# Esquematico.net
KiCad netlist of a schematic drawn in Altium Designer
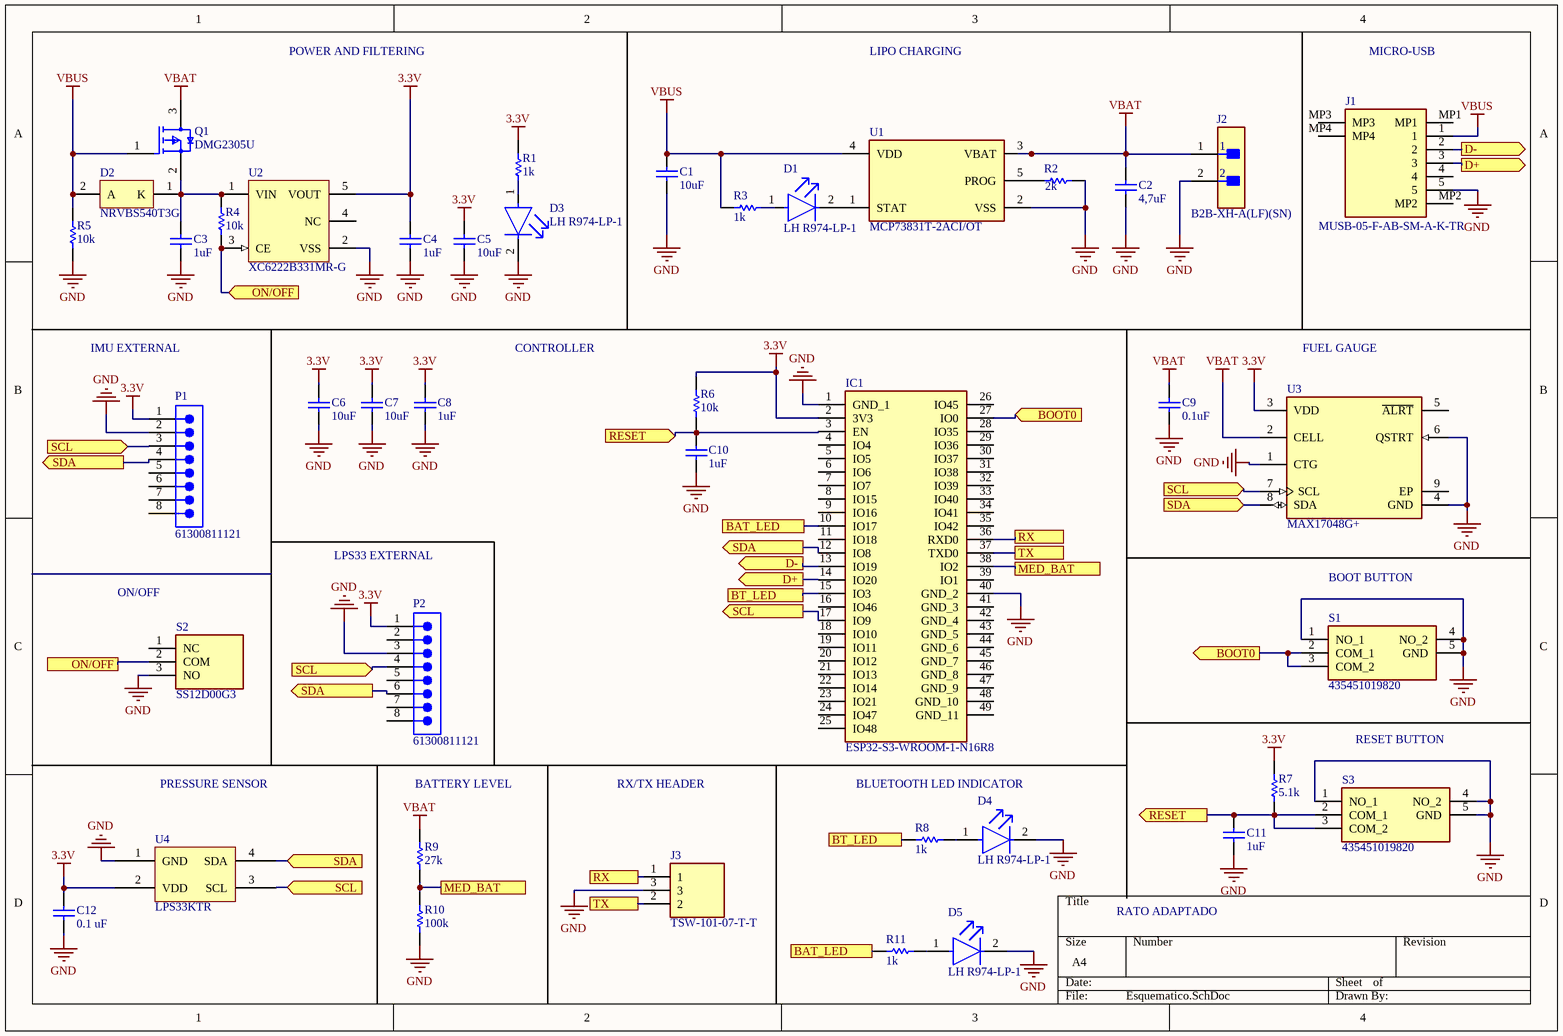
[diagram p0: Esquematico.SchDoc]

(export (version "E")
  (design (tool "Eeschema 10.0.6"))
  (components
    (comp (ref "C1")
      (value "10uF")
      (footprint "CAPC2013X88X50LL20T25")
      (fields (field (name "MANUFACTURER") "Kemet") (field (name "PART NUMBER") "C0805C103K5RACTU"))
      (libsource (lib "Altium Content Vault") (part "CAP"))
    )
    (comp (ref "C2")
      (value "4,7uF")
      (footprint "CAPC2013X88X50LL20T25")
      (fields (field (name "MANUFACTURER") "Kemet") (field (name "PART NUMBER") "C0805C103K5RACTU"))
      (libsource (lib "Altium Content Vault") (part "CAP"))
    )
    (comp (ref "C3")
      (value "1uF")
      (footprint "CAPC2013X88X50LL20T25")
      (fields (field (name "MANUFACTURER") "Kemet") (field (name "PART NUMBER") "C0805C103K5RACTU"))
      (libsource (lib "Altium Content Vault") (part "CAP"))
    )
    (comp (ref "C4")
      (value "1uF")
      (footprint "CAPC2013X88X50LL20T25")
      (fields (field (name "MANUFACTURER") "Kemet") (field (name "PART NUMBER") "C0805C103K5RACTU"))
      (libsource (lib "Altium Content Vault") (part "CAP"))
    )
    (comp (ref "C5")
      (value "10uF")
      (footprint "CAPC2013X88X50LL20T25")
      (fields (field (name "MANUFACTURER") "Kemet") (field (name "PART NUMBER") "C0805C103K5RACTU"))
      (libsource (lib "Altium Content Vault") (part "CAP"))
    )
    (comp (ref "C6")
      (value "10uF")
      (footprint "CAPC2013X88X50LL20T25")
      (fields (field (name "MANUFACTURER") "Kemet") (field (name "PART NUMBER") "C0805C103K5RACTU"))
      (libsource (lib "Altium Content Vault") (part "CAP"))
    )
    (comp (ref "C7")
      (value "10uF")
      (footprint "CAPC2013X88X50LL20T25")
      (fields (field (name "MANUFACTURER") "Kemet") (field (name "PART NUMBER") "C0805C103K5RACTU"))
      (libsource (lib "Altium Content Vault") (part "CAP"))
    )
    (comp (ref "C8")
      (value "1uF")
      (footprint "CAPC2013X88X50LL20T25")
      (fields (field (name "MANUFACTURER") "Kemet") (field (name "PART NUMBER") "C0805C103K5RACTU"))
      (libsource (lib "Altium Content Vault") (part "CAP"))
    )
    (comp (ref "C9")
      (value "0.1uF")
      (footprint "CAPC2013X88X50LL20T25")
      (fields (field (name "MANUFACTURER") "Kemet") (field (name "PART NUMBER") "C0805C103K5RACTU"))
      (libsource (lib "Altium Content Vault") (part "CAP"))
    )
    (comp (ref "C10")
      (value "1uF")
      (footprint "CAPC2013X88X50LL20T25")
      (fields (field (name "MANUFACTURER") "Kemet") (field (name "PART NUMBER") "C0805C103K5RACTU"))
      (libsource (lib "Altium Content Vault") (part "CAP"))
    )
    (comp (ref "C11")
      (value "1uF")
      (footprint "CAPC2013X88X50LL20T25")
      (fields (field (name "MANUFACTURER") "Kemet") (field (name "PART NUMBER") "C0805C103K5RACTU"))
      (libsource (lib "Altium Content Vault") (part "CAP"))
    )
    (comp (ref "C12")
      (value "0.1 uF")
      (footprint "CAPC2013X88X50LL20T25")
      (fields (field (name "MANUFACTURER") "Kemet") (field (name "PART NUMBER") "C0805C103K5RACTU"))
      (libsource (lib "Altium Content Vault") (part "CAP"))
    )
    (comp (ref "D1")
      (value "LH R974-LP-1")
      (footprint "FP-LH_R974-MFG")
      (description "LED RED DIFFUSED 0805 SMD")
      (libsource (lib "Altium Content Vault") (part "ab1c01a81903e929fc6c44469aada92"))
    )
    (comp (ref "D2")
      (value "NRVBS540T3G")
      (footprint "ONSC-SMC-2-403-03_V")
      (description "Schottky Power Rectifier, 2-Pin SMC, Pb-Free, Tape and Reel")
      (fields (field (name "MANUFACTURER") "On Semiconductor"))
      (libsource (lib "Altium Content Vault") (part "ONSC-D-K1A2-2_A"))
    )
    (comp (ref "D3")
      (value "LH R974-LP-1")
      (footprint "FP-LH_R974-MFG")
      (description "LED RED DIFFUSED 0805 SMD")
      (libsource (lib "Altium Content Vault") (part "ab1c01a81903e929fc6c44469aada92"))
    )
    (comp (ref "D4")
      (value "LH R974-LP-1")
      (footprint "FP-LH_R974-MFG")
      (description "LED RED DIFFUSED 0805 SMD")
      (libsource (lib "Altium Content Vault") (part "ab1c01a81903e929fc6c44469aada92"))
    )
    (comp (ref "D5")
      (value "LH R974-LP-1")
      (footprint "FP-LH_R974-MFG")
      (description "LED RED DIFFUSED 0805 SMD")
      (libsource (lib "Altium Content Vault") (part "ab1c01a81903e929fc6c44469aada92"))
    )
    (comp (ref "IC1")
      (value "ESP32-S3-WROOM-1-N16R8")
      (footprint "SamacSys:ESP32S3WROOM1N16R8")
      (description "Integrated Circuit")
      (fields (field (name "MOUSER PART NUMBER") "356-ESP32S3WRM1N16R8"))
      (libsource (lib "*") (part "ESP32-S3-WROOM-1-N16R8"))
    )
    (comp (ref "J1")
      (value "MUSB-05-F-AB-SM-A-K-TR")
      (footprint "SamacSys:MUSB05FABSMAKTR")
      (description "Connector")
      (fields (field (name "MOUSER PART NUMBER") "200-MUSB05FABSMAKTR"))
      (libsource (lib "*") (part "MUSB-05-F-AB-SM-A-K-TR"))
    )
    (comp (ref "J2")
      (value "B2B-XH-A(LF)(SN)")
      (footprint "FP-B2B-XH-A_LF_SN-MFG")
      (description "CONN HEADER VERT 2POS 2.5MM")
      (libsource (lib "Altium Content Vault") (part "3bc925449376181038e59eaffc5286c"))
    )
    (comp (ref "J3")
      (value "TSW-101-07-T-T")
      (footprint "SamacSys:HDRV3W64P254_3X1_254X762X838P")
      (description "Connector")
      (libsource (lib "*") (part "TSW-101-07-T-T"))
    )
    (comp (ref "P1")
      (value "61300811121")
      (footprint "61300811121")
      (libsource (lib "Altium Content Vault") (part "Header_Male_1R_08P"))
    )
    (comp (ref "P2")
      (value "61300811121")
      (footprint "61300811121")
      (libsource (lib "Altium Content Vault") (part "Header_Male_1R_08P"))
    )
    (comp (ref "Q1")
      (value "DMG2305U")
      (footprint "FP-SOT23-MFG")
      (description "MOSFET P-CH 20V 4.2A SOT23")
      (fields
        (field (name "MANUFACTURER") "Diodes Inc.")
        (field (name "MANUFACTURER PART NUMBER") "DMG2305UX-13")
      )
      (libsource (lib "Altium Content Vault") (part "b298ed0aef6ca29edb293456b19cad3"))
    )
    (comp (ref "R1")
      (value "1k")
      (footprint "RESC2013X50X30LL20T20")
      (fields (field (name "MANUFACTURER") "Vishay Dale") (field (name "PART NUMBER") "CRCW08050000Z0EA"))
      (libsource (lib "Altium Content Vault") (part "RES"))
    )
    (comp (ref "R2")
      (value "2k")
      (footprint "RESC2013X50X30LL20T20")
      (fields (field (name "MANUFACTURER") "Vishay Dale") (field (name "PART NUMBER") "CRCW08050000Z0EA"))
      (libsource (lib "Altium Content Vault") (part "RES"))
    )
    (comp (ref "R3")
      (value "1k")
      (footprint "RESC2013X50X30LL20T20")
      (fields (field (name "MANUFACTURER") "Vishay Dale") (field (name "PART NUMBER") "CRCW08050000Z0EA"))
      (libsource (lib "Altium Content Vault") (part "RES"))
    )
    (comp (ref "R4")
      (value "10k")
      (footprint "RESC2013X50X30LL20T20")
      (fields (field (name "MANUFACTURER") "Vishay Dale") (field (name "PART NUMBER") "CRCW08050000Z0EA"))
      (libsource (lib "Altium Content Vault") (part "RES"))
    )
    (comp (ref "R5")
      (value "10k")
      (footprint "RESC2013X50X30LL20T20")
      (fields (field (name "MANUFACTURER") "Vishay Dale") (field (name "PART NUMBER") "CRCW08050000Z0EA"))
      (libsource (lib "Altium Content Vault") (part "RES"))
    )
    (comp (ref "R6")
      (value "10k")
      (footprint "RESC2013X50X30LL20T20")
      (fields (field (name "MANUFACTURER") "Vishay Dale") (field (name "PART NUMBER") "CRCW08050000Z0EA"))
      (libsource (lib "Altium Content Vault") (part "RES"))
    )
    (comp (ref "R7")
      (value "5.1k")
      (footprint "RESC2013X50X30LL20T20")
      (fields (field (name "MANUFACTURER") "Vishay Dale") (field (name "PART NUMBER") "CRCW08050000Z0EA"))
      (libsource (lib "Altium Content Vault") (part "RES"))
    )
    (comp (ref "R8")
      (value "1k")
      (footprint "RESC2013X50X30LL20T20")
      (fields (field (name "MANUFACTURER") "Vishay Dale") (field (name "PART NUMBER") "CRCW08050000Z0EA"))
      (libsource (lib "Altium Content Vault") (part "RES"))
    )
    (comp (ref "R9")
      (value "27k")
      (footprint "RESC2013X50X30LL20T20")
      (fields (field (name "MANUFACTURER") "Vishay Dale") (field (name "PART NUMBER") "CRCW08050000Z0EA"))
      (libsource (lib "Altium Content Vault") (part "RES"))
    )
    (comp (ref "R10")
      (value "100k")
      (footprint "RESC2013X50X30LL20T20")
      (fields (field (name "MANUFACTURER") "Vishay Dale") (field (name "PART NUMBER") "CRCW08050000Z0EA"))
      (libsource (lib "Altium Content Vault") (part "RES"))
    )
    (comp (ref "R11")
      (value "1k")
      (footprint "RESC2013X50X30LL20T20")
      (fields (field (name "MANUFACTURER") "Vishay Dale") (field (name "PART NUMBER") "CRCW08050000Z0EA"))
      (libsource (lib "Altium Content Vault") (part "RES"))
    )
    (comp (ref "S1")
      (value "435451019820")
      (footprint "SamacSys:435451019820")
      (description "Switch")
      (fields (field (name "MOUSER PART NUMBER") "710-435451019820"))
      (libsource (lib "*") (part "435451019820"))
    )
    (comp (ref "S2")
      (value "SS12D00G3")
      (footprint "SamacSys:SS12D00G3")
      (description "Switch")
      (libsource (lib "*") (part "SS12D00G3"))
    )
    (comp (ref "S3")
      (value "435451019820")
      (footprint "SamacSys:435451019820")
      (description "Switch")
      (fields (field (name "MOUSER PART NUMBER") "710-435451019820"))
      (libsource (lib "*") (part "435451019820"))
    )
    (comp (ref "U1")
      (value "MCP73831T-2ACI/OT")
      (footprint "FP-C04-091-OT-IPC_B")
      (description "IC CONTROLLR LI-ION 4.2V SOT23-5")
      (libsource (lib "Altium Content Vault") (part "61f5a3bb3429d9e0caadea342aa3b19"))
    )
    (comp (ref "U2")
      (value "XC6222B331MR-G")
      (footprint "TORX-SOT-25-5_L")
      (description "High Speed LDO Regulator, 700 mA, 1.7 to 6.0 V, -40 to 85 degC, SOT-25 (MR-G), RoHS, Tape and Reel")
      (fields (field (name "MANUFACTURER") "Torex"))
      (libsource (lib "Altium Content Vault") (part "TORX-XC6222-SOT-25-5"))
    )
    (comp (ref "U3")
      (value "MAX17048G+")
      (footprint "FP-T822-3-MFG")
      (description "IC BATT MON LI-ION 1CELL 8TDFN")
      (libsource (lib "Altium Content Vault") (part "2e5dfe4d6b6c3eae1d63c902a28205a"))
    )
    (comp (ref "U4") (value "LPS33KTR") (footprint "LPS33KTR") (libsource (lib "LPS33KTR") (part "LPS33KTR")))
  )
  (nets
    (net (code "1") (name "/BAT_LED") (class "Default")
      (node (ref "IC1") (pin "10") (pinfunction "IO17_10") (pintype "passive"))
      (node (ref "R11") (pin "2") (pinfunction "2_2") (pintype "passive"))
    )
    (net (code "2") (name "/BOOT0") (class "Default")
      (node (ref "IC1") (pin "27") (pinfunction "IO0_27") (pintype "passive"))
      (node (ref "S1") (pin "2") (pinfunction "COM_1_2") (pintype "passive"))
      (node (ref "S1") (pin "3") (pinfunction "COM_2_3") (pintype "passive"))
    )
    (net (code "3") (name "/BT_LED") (class "Default")
      (node (ref "IC1") (pin "15") (pinfunction "IO3_15") (pintype "passive"))
      (node (ref "R8") (pin "2") (pinfunction "2_2") (pintype "passive"))
    )
    (net (code "4") (name "/D+") (class "Default")
      (node (ref "IC1") (pin "14") (pinfunction "IO20_14") (pintype "passive"))
      (node (ref "J1") (pin "3") (pinfunction "3_3") (pintype "passive"))
    )
    (net (code "5") (name "/D-") (class "Default")
      (node (ref "IC1") (pin "13") (pinfunction "IO19_13") (pintype "passive"))
      (node (ref "J1") (pin "2") (pinfunction "2_2") (pintype "passive"))
    )
    (net (code "6") (name "/MED_BAT") (class "Default")
      (node (ref "IC1") (pin "38") (pinfunction "IO2_38") (pintype "passive"))
      (node (ref "R10") (pin "2") (pinfunction "2_2") (pintype "passive"))
      (node (ref "R9") (pin "1") (pinfunction "1_1") (pintype "passive"))
    )
    (net (code "7") (name "/ON{slash}OFF") (class "Default")
      (node (ref "R4") (pin "1") (pinfunction "1_1") (pintype "passive"))
      (node (ref "S2") (pin "2") (pinfunction "COM_2") (pintype "passive"))
      (node (ref "U2") (pin "3") (pinfunction "CE_3") (pintype "input"))
    )
    (net (code "8") (name "/RESET") (class "Default")
      (node (ref "C10") (pin "2") (pinfunction "2_2") (pintype "passive"))
      (node (ref "C11") (pin "2") (pinfunction "2_2") (pintype "passive"))
      (node (ref "IC1") (pin "3") (pinfunction "EN_3") (pintype "passive"))
      (node (ref "R6") (pin "1") (pinfunction "1_1") (pintype "passive"))
      (node (ref "R7") (pin "2") (pinfunction "2_2") (pintype "passive"))
      (node (ref "S3") (pin "2") (pinfunction "COM_1_2") (pintype "passive"))
      (node (ref "S3") (pin "3") (pinfunction "COM_2_3") (pintype "passive"))
    )
    (net (code "9") (name "/RX") (class "Default")
      (node (ref "IC1") (pin "36") (pinfunction "RXD0_36") (pintype "passive"))
      (node (ref "J3") (pin "1") (pinfunction "1_1") (pintype "passive"))
    )
    (net (code "10") (name "/SCL") (class "Default")
      (node (ref "IC1") (pin "17") (pinfunction "IO9_17") (pintype "passive"))
      (node (ref "P1") (pin "3") (pinfunction "3_3") (pintype "passive"))
      (node (ref "P2") (pin "4") (pinfunction "4_4") (pintype "passive"))
      (node (ref "U3") (pin "7") (pinfunction "SCL_7") (pintype "input"))
      (node (ref "U4") (pin "3") (pinfunction "SCL_3") (pintype "passive"))
    )
    (net (code "11") (name "/SDA") (class "Default")
      (node (ref "IC1") (pin "12") (pinfunction "IO8_12") (pintype "passive"))
      (node (ref "P1") (pin "4") (pinfunction "4_4") (pintype "passive"))
      (node (ref "P2") (pin "6") (pinfunction "6_6") (pintype "passive"))
      (node (ref "U3") (pin "8") (pinfunction "SDA_8") (pintype "bidirectional"))
      (node (ref "U4") (pin "4") (pinfunction "SDA_4") (pintype "passive"))
    )
    (net (code "12") (name "/TX") (class "Default")
      (node (ref "IC1") (pin "37") (pinfunction "TXD0_37") (pintype "passive"))
      (node (ref "J3") (pin "2") (pinfunction "2_2") (pintype "passive"))
    )
    (net (code "13") (name "3.3V") (class "Default")
      (node (ref "C12") (pin "1") (pinfunction "1_1") (pintype "passive"))
      (node (ref "C4") (pin "2") (pinfunction "2_2") (pintype "passive"))
      (node (ref "C5") (pin "2") (pinfunction "2_2") (pintype "passive"))
      (node (ref "C6") (pin "2") (pinfunction "2_2") (pintype "passive"))
      (node (ref "C7") (pin "2") (pinfunction "2_2") (pintype "passive"))
      (node (ref "C8") (pin "2") (pinfunction "2_2") (pintype "passive"))
      (node (ref "IC1") (pin "2") (pinfunction "3V3_2") (pintype "passive"))
      (node (ref "P1") (pin "1") (pinfunction "1_1") (pintype "passive"))
      (node (ref "P2") (pin "1") (pinfunction "1_1") (pintype "passive"))
      (node (ref "R1") (pin "2") (pinfunction "2_2") (pintype "passive"))
      (node (ref "R6") (pin "2") (pinfunction "2_2") (pintype "passive"))
      (node (ref "R7") (pin "1") (pinfunction "1_1") (pintype "passive"))
      (node (ref "U2") (pin "5") (pinfunction "VOUT_5") (pintype "power_in"))
      (node (ref "U3") (pin "3") (pinfunction "VDD_3") (pintype "power_in"))
      (node (ref "U4") (pin "2") (pinfunction "VDD_2") (pintype "passive"))
    )
    (net (code "14") (name "GND") (class "Default")
      (node (ref "C1") (pin "1") (pinfunction "1_1") (pintype "passive"))
      (node (ref "C10") (pin "1") (pinfunction "1_1") (pintype "passive"))
      (node (ref "C11") (pin "1") (pinfunction "1_1") (pintype "passive"))
      (node (ref "C12") (pin "2") (pinfunction "2_2") (pintype "passive"))
      (node (ref "C2") (pin "1") (pinfunction "1_1") (pintype "passive"))
      (node (ref "C3") (pin "1") (pinfunction "1_1") (pintype "passive"))
      (node (ref "C4") (pin "1") (pinfunction "1_1") (pintype "passive"))
      (node (ref "C5") (pin "1") (pinfunction "1_1") (pintype "passive"))
      (node (ref "C6") (pin "1") (pinfunction "1_1") (pintype "passive"))
      (node (ref "C7") (pin "1") (pinfunction "1_1") (pintype "passive"))
      (node (ref "C8") (pin "1") (pinfunction "1_1") (pintype "passive"))
      (node (ref "C9") (pin "1") (pinfunction "1_1") (pintype "passive"))
      (node (ref "D3") (pin "2") (pinfunction "C_2") (pintype "passive"))
      (node (ref "D4") (pin "2") (pinfunction "C_2") (pintype "passive"))
      (node (ref "D5") (pin "2") (pinfunction "C_2") (pintype "passive"))
      (node (ref "IC1") (pin "1") (pinfunction "GND_1_1") (pintype "passive"))
      (node (ref "IC1") (pin "40") (pinfunction "GND_2_40") (pintype "passive"))
      (node (ref "J1") (pin "5") (pinfunction "5_5") (pintype "passive"))
      (node (ref "J2") (pin "2") (pinfunction "2_2") (pintype "passive"))
      (node (ref "J3") (pin "3") (pinfunction "3_3") (pintype "passive"))
      (node (ref "P1") (pin "2") (pinfunction "2_2") (pintype "passive"))
      (node (ref "P2") (pin "3") (pinfunction "3_3") (pintype "passive"))
      (node (ref "R10") (pin "1") (pinfunction "1_1") (pintype "passive"))
      (node (ref "R2") (pin "1") (pinfunction "1_1") (pintype "passive"))
      (node (ref "R5") (pin "1") (pinfunction "1_1") (pintype "passive"))
      (node (ref "S1") (pin "1") (pinfunction "NO_1_1") (pintype "passive"))
      (node (ref "S1") (pin "4") (pinfunction "NO_2_4") (pintype "passive"))
      (node (ref "S1") (pin "5") (pinfunction "GND_5") (pintype "passive"))
      (node (ref "S2") (pin "3") (pinfunction "NO_3") (pintype "passive"))
      (node (ref "S3") (pin "1") (pinfunction "NO_1_1") (pintype "passive"))
      (node (ref "S3") (pin "4") (pinfunction "NO_2_4") (pintype "passive"))
      (node (ref "S3") (pin "5") (pinfunction "GND_5") (pintype "passive"))
      (node (ref "U1") (pin "2") (pinfunction "VSS_2") (pintype "power_in"))
      (node (ref "U2") (pin "2") (pinfunction "VSS_2") (pintype "power_in"))
      (node (ref "U3") (pin "1") (pinfunction "CTG_1") (pintype "power_in"))
      (node (ref "U3") (pin "4") (pinfunction "GND_4") (pintype "power_in"))
      (node (ref "U3") (pin "6") (pinfunction "QSTRT_6") (pintype "input"))
      (node (ref "U4") (pin "1") (pinfunction "GND_1") (pintype "passive"))
    )
    (net (code "15") (name "Net-(D1-A)") (class "Default")
      (node (ref "D1") (pin "1") (pinfunction "A_1") (pintype "passive"))
      (node (ref "R3") (pin "1") (pinfunction "1_1") (pintype "passive"))
    )
    (net (code "16") (name "Net-(D1-C)") (class "Default")
      (node (ref "D1") (pin "2") (pinfunction "C_2") (pintype "passive"))
      (node (ref "U1") (pin "1") (pinfunction "STAT_1") (pintype "passive"))
    )
    (net (code "17") (name "Net-(D2-K)") (class "Default")
      (node (ref "C3") (pin "2") (pinfunction "2_2") (pintype "passive"))
      (node (ref "D2") (pin "1") (pinfunction "K_1") (pintype "passive"))
      (node (ref "Q1") (pin "2") (pinfunction "S_2") (pintype "passive"))
      (node (ref "R4") (pin "2") (pinfunction "2_2") (pintype "passive"))
      (node (ref "U2") (pin "1") (pinfunction "VIN_1") (pintype "power_in"))
    )
    (net (code "18") (name "Net-(D3-A)") (class "Default")
      (node (ref "D3") (pin "1") (pinfunction "A_1") (pintype "passive"))
      (node (ref "R1") (pin "1") (pinfunction "1_1") (pintype "passive"))
    )
    (net (code "19") (name "Net-(D4-A)") (class "Default")
      (node (ref "D4") (pin "1") (pinfunction "A_1") (pintype "passive"))
      (node (ref "R8") (pin "1") (pinfunction "1_1") (pintype "passive"))
    )
    (net (code "20") (name "Net-(D5-A)") (class "Default")
      (node (ref "D5") (pin "1") (pinfunction "A_1") (pintype "passive"))
      (node (ref "R11") (pin "1") (pinfunction "1_1") (pintype "passive"))
    )
    (net (code "21") (name "Net-(U1-PROG)") (class "Default")
      (node (ref "R2") (pin "2") (pinfunction "2_2") (pintype "passive"))
      (node (ref "U1") (pin "5") (pinfunction "PROG_5") (pintype "passive"))
    )
    (net (code "22") (name "VBAT") (class "Default")
      (node (ref "C2") (pin "2") (pinfunction "2_2") (pintype "passive"))
      (node (ref "C9") (pin "2") (pinfunction "2_2") (pintype "passive"))
      (node (ref "J2") (pin "1") (pinfunction "1_1") (pintype "passive"))
      (node (ref "Q1") (pin "3") (pinfunction "D_3") (pintype "passive"))
      (node (ref "R9") (pin "2") (pinfunction "2_2") (pintype "passive"))
      (node (ref "U1") (pin "3") (pinfunction "VBAT_3") (pintype "power_in"))
      (node (ref "U3") (pin "2") (pinfunction "CELL_2") (pintype "power_in"))
    )
    (net (code "23") (name "VBUS") (class "Default")
      (node (ref "C1") (pin "2") (pinfunction "2_2") (pintype "passive"))
      (node (ref "D2") (pin "2") (pinfunction "A_2") (pintype "passive"))
      (node (ref "J1") (pin "1") (pinfunction "1_1") (pintype "passive"))
      (node (ref "Q1") (pin "1") (pinfunction "G_1") (pintype "passive"))
      (node (ref "R3") (pin "2") (pinfunction "2_2") (pintype "passive"))
      (node (ref "R5") (pin "2") (pinfunction "2_2") (pintype "passive"))
      (node (ref "U1") (pin "4") (pinfunction "VDD_4") (pintype "power_in"))
    )
    (net (code "24") (name "unconnected-(IC1-GND_3-Pad41)") (class "Default")
      (node (ref "IC1") (pin "41") (pinfunction "GND_3_41") (pintype "passive"))
    )
    (net (code "25") (name "unconnected-(IC1-GND_4-Pad42)") (class "Default")
      (node (ref "IC1") (pin "42") (pinfunction "GND_4_42") (pintype "passive"))
    )
    (net (code "26") (name "unconnected-(IC1-GND_5-Pad43)") (class "Default")
      (node (ref "IC1") (pin "43") (pinfunction "GND_5_43") (pintype "passive"))
    )
    (net (code "27") (name "unconnected-(IC1-GND_6-Pad44)") (class "Default")
      (node (ref "IC1") (pin "44") (pinfunction "GND_6_44") (pintype "passive"))
    )
    (net (code "28") (name "unconnected-(IC1-GND_7-Pad45)") (class "Default")
      (node (ref "IC1") (pin "45") (pinfunction "GND_7_45") (pintype "passive"))
    )
    (net (code "29") (name "unconnected-(IC1-GND_8-Pad46)") (class "Default")
      (node (ref "IC1") (pin "46") (pinfunction "GND_8_46") (pintype "passive"))
    )
    (net (code "30") (name "unconnected-(IC1-GND_9-Pad47)") (class "Default")
      (node (ref "IC1") (pin "47") (pinfunction "GND_9_47") (pintype "passive"))
    )
    (net (code "31") (name "unconnected-(IC1-GND_10-Pad48)") (class "Default")
      (node (ref "IC1") (pin "48") (pinfunction "GND_10_48") (pintype "passive"))
    )
    (net (code "32") (name "unconnected-(IC1-GND_11-Pad49)") (class "Default")
      (node (ref "IC1") (pin "49") (pinfunction "GND_11_49") (pintype "passive"))
    )
    (net (code "33") (name "unconnected-(IC1-IO1-Pad39)") (class "Default")
      (node (ref "IC1") (pin "39") (pinfunction "IO1_39") (pintype "passive"))
    )
    (net (code "34") (name "unconnected-(IC1-IO4-Pad4)") (class "Default")
      (node (ref "IC1") (pin "4") (pinfunction "IO4_4") (pintype "passive"))
    )
    (net (code "35") (name "unconnected-(IC1-IO5-Pad5)") (class "Default")
      (node (ref "IC1") (pin "5") (pinfunction "IO5_5") (pintype "passive"))
    )
    (net (code "36") (name "unconnected-(IC1-IO6-Pad6)") (class "Default")
      (node (ref "IC1") (pin "6") (pinfunction "IO6_6") (pintype "passive"))
    )
    (net (code "37") (name "unconnected-(IC1-IO7-Pad7)") (class "Default")
      (node (ref "IC1") (pin "7") (pinfunction "IO7_7") (pintype "passive"))
    )
    (net (code "38") (name "unconnected-(IC1-IO10-Pad18)") (class "Default")
      (node (ref "IC1") (pin "18") (pinfunction "IO10_18") (pintype "passive"))
    )
    (net (code "39") (name "unconnected-(IC1-IO11-Pad19)") (class "Default")
      (node (ref "IC1") (pin "19") (pinfunction "IO11_19") (pintype "passive"))
    )
    (net (code "40") (name "unconnected-(IC1-IO12-Pad20)") (class "Default")
      (node (ref "IC1") (pin "20") (pinfunction "IO12_20") (pintype "passive"))
    )
    (net (code "41") (name "unconnected-(IC1-IO13-Pad21)") (class "Default")
      (node (ref "IC1") (pin "21") (pinfunction "IO13_21") (pintype "passive"))
    )
    (net (code "42") (name "unconnected-(IC1-IO14-Pad22)") (class "Default")
      (node (ref "IC1") (pin "22") (pinfunction "IO14_22") (pintype "passive"))
    )
    (net (code "43") (name "unconnected-(IC1-IO15-Pad8)") (class "Default")
      (node (ref "IC1") (pin "8") (pinfunction "IO15_8") (pintype "passive"))
    )
    (net (code "44") (name "unconnected-(IC1-IO16-Pad9)") (class "Default")
      (node (ref "IC1") (pin "9") (pinfunction "IO16_9") (pintype "passive"))
    )
    (net (code "45") (name "unconnected-(IC1-IO18-Pad11)") (class "Default")
      (node (ref "IC1") (pin "11") (pinfunction "IO18_11") (pintype "passive"))
    )
    (net (code "46") (name "unconnected-(IC1-IO21-Pad23)") (class "Default")
      (node (ref "IC1") (pin "23") (pinfunction "IO21_23") (pintype "passive"))
    )
    (net (code "47") (name "unconnected-(IC1-IO35-Pad28)") (class "Default")
      (node (ref "IC1") (pin "28") (pinfunction "IO35_28") (pintype "passive"))
    )
    (net (code "48") (name "unconnected-(IC1-IO36-Pad29)") (class "Default")
      (node (ref "IC1") (pin "29") (pinfunction "IO36_29") (pintype "passive"))
    )
    (net (code "49") (name "unconnected-(IC1-IO37-Pad30)") (class "Default")
      (node (ref "IC1") (pin "30") (pinfunction "IO37_30") (pintype "passive"))
    )
    (net (code "50") (name "unconnected-(IC1-IO38-Pad31)") (class "Default")
      (node (ref "IC1") (pin "31") (pinfunction "IO38_31") (pintype "passive"))
    )
    (net (code "51") (name "unconnected-(IC1-IO39-Pad32)") (class "Default")
      (node (ref "IC1") (pin "32") (pinfunction "IO39_32") (pintype "passive"))
    )
    (net (code "52") (name "unconnected-(IC1-IO40-Pad33)") (class "Default")
      (node (ref "IC1") (pin "33") (pinfunction "IO40_33") (pintype "passive"))
    )
    (net (code "53") (name "unconnected-(IC1-IO41-Pad34)") (class "Default")
      (node (ref "IC1") (pin "34") (pinfunction "IO41_34") (pintype "passive"))
    )
    (net (code "54") (name "unconnected-(IC1-IO42-Pad35)") (class "Default")
      (node (ref "IC1") (pin "35") (pinfunction "IO42_35") (pintype "passive"))
    )
    (net (code "55") (name "unconnected-(IC1-IO45-Pad26)") (class "Default")
      (node (ref "IC1") (pin "26") (pinfunction "IO45_26") (pintype "passive"))
    )
    (net (code "56") (name "unconnected-(IC1-IO46-Pad16)") (class "Default")
      (node (ref "IC1") (pin "16") (pinfunction "IO46_16") (pintype "passive"))
    )
    (net (code "57") (name "unconnected-(IC1-IO47-Pad24)") (class "Default")
      (node (ref "IC1") (pin "24") (pinfunction "IO47_24") (pintype "passive"))
    )
    (net (code "58") (name "unconnected-(IC1-IO48-Pad25)") (class "Default")
      (node (ref "IC1") (pin "25") (pinfunction "IO48_25") (pintype "passive"))
    )
    (net (code "59") (name "unconnected-(J1-Pad4)") (class "Default")
      (node (ref "J1") (pin "4") (pinfunction "4_4") (pintype "passive"))
    )
    (net (code "60") (name "unconnected-(J1-PadMP1)") (class "Default")
      (node (ref "J1") (pin "MP1") (pinfunction "MP1_MP1") (pintype "passive"))
    )
    (net (code "61") (name "unconnected-(J1-PadMP2)") (class "Default")
      (node (ref "J1") (pin "MP2") (pinfunction "MP2_MP2") (pintype "passive"))
    )
    (net (code "62") (name "unconnected-(J1-PadMP3)") (class "Default")
      (node (ref "J1") (pin "MP3") (pinfunction "MP3_MP3") (pintype "passive"))
    )
    (net (code "63") (name "unconnected-(J1-PadMP4)") (class "Default")
      (node (ref "J1") (pin "MP4") (pinfunction "MP4_MP4") (pintype "passive"))
    )
    (net (code "64") (name "unconnected-(P1-Pad5)") (class "Default")
      (node (ref "P1") (pin "5") (pinfunction "5_5") (pintype "passive"))
    )
    (net (code "65") (name "unconnected-(P1-Pad6)") (class "Default")
      (node (ref "P1") (pin "6") (pinfunction "6_6") (pintype "passive"))
    )
    (net (code "66") (name "unconnected-(P1-Pad7)") (class "Default")
      (node (ref "P1") (pin "7") (pinfunction "7_7") (pintype "passive"))
    )
    (net (code "67") (name "unconnected-(P1-Pad8)") (class "Default")
      (node (ref "P1") (pin "8") (pinfunction "8_8") (pintype "passive"))
    )
    (net (code "68") (name "unconnected-(P2-Pad2)") (class "Default")
      (node (ref "P2") (pin "2") (pinfunction "2_2") (pintype "passive"))
    )
    (net (code "69") (name "unconnected-(P2-Pad5)") (class "Default")
      (node (ref "P2") (pin "5") (pinfunction "5_5") (pintype "passive"))
    )
    (net (code "70") (name "unconnected-(P2-Pad7)") (class "Default")
      (node (ref "P2") (pin "7") (pinfunction "7_7") (pintype "passive"))
    )
    (net (code "71") (name "unconnected-(P2-Pad8)") (class "Default")
      (node (ref "P2") (pin "8") (pinfunction "8_8") (pintype "passive"))
    )
    (net (code "72") (name "unconnected-(S2-NC-Pad1)") (class "Default")
      (node (ref "S2") (pin "1") (pinfunction "NC_1") (pintype "passive"))
    )
    (net (code "73") (name "unconnected-(U2-NC-Pad4)") (class "Default")
      (node (ref "U2") (pin "4") (pinfunction "NC_4") (pintype "passive"))
    )
    (net (code "74") (name "unconnected-(U3-EP-Pad9)") (class "Default")
      (node (ref "U3") (pin "9") (pinfunction "EP_9") (pintype "power_in"))
    )
    (net (code "75") (name "unconnected-(U3-~{ALRT}-Pad5)") (class "Default")
      (node (ref "U3") (pin "5") (pinfunction "~{ALRT}_5") (pintype "open_collector"))
    )
  )
)
